# 3V3Supply.net
KiCad netlist of a schematic drawn in Altium Designer
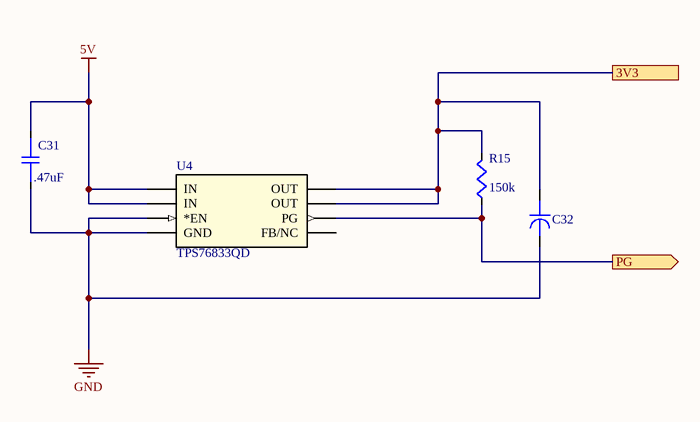
[diagram p0: 3V3Supply.SchDoc]

(export (version "E")
  (design (tool "Eeschema 10.0.6"))
  (components
    (comp (ref "C31")
      (value ".47uF")
      (footprint "C0603")
      (description "KEMET - C0603C474J4RACAUTO - CAP, 0.47µF, 16V, 5%, X7R, 0603")
      (fields (field (name "TOLERANCE") "5%"))
      (libsource (lib "DAQ") (part "C0603C474J4RACAUTO"))
    )
    (comp (ref "C32")
      (value "22UF TANT")
      (footprint "CAP_293D_D_VIS")
      (description "CAP TANT 22UF 10% 35V 2917")
      (fields (field (name "TOLERANCE") "10%") (field (name "VOLTAGE") "35V"))
      (libsource (lib "DAQ") (part "293D226X9035D2TE3"))
    )
    (comp (ref "R15")
      (value "150k")
      (footprint "R0603")
      (description "CRGCQ 0603 150K 1%")
      (fields (field (name "TOLERANCE") "5%"))
      (libsource (lib "DAQ") (part "CRGCQ0603F150K"))
    )
    (comp (ref "U4")
      (value "TPS76833QD")
      (footprint "D8_TEX")
      (description "3.3V Linear Voltage Regulator IC 1 Output 1A 8-SOIC")
      (fields (field (name "COPYRIGHT") "Copyright (C) 2018 Accelerated Designs. All rights reserved"))
      (libsource (lib "DAQ") (part "TPS76833QD"))
    )
  )
  (nets
    (net (code "1") (name "/3V3") (class "Default")
      (node (ref "C32") (pin "2") (pinfunction "2_2") (pintype "passive"))
      (node (ref "R15") (pin "2") (pinfunction "2_2") (pintype "passive"))
      (node (ref "U4") (pin "5") (pinfunction "OUT_5") (pintype "power_in"))
      (node (ref "U4") (pin "6") (pinfunction "OUT_6") (pintype "power_in"))
    )
    (net (code "2") (name "/PG") (class "Default")
      (node (ref "R15") (pin "1") (pinfunction "1_1") (pintype "passive"))
      (node (ref "U4") (pin "8") (pinfunction "PG_8") (pintype "output"))
    )
    (net (code "3") (name "5V") (class "Default")
      (node (ref "C31") (pin "2") (pinfunction "2_2") (pintype "passive"))
      (node (ref "U4") (pin "3") (pinfunction "IN_3") (pintype "power_in"))
      (node (ref "U4") (pin "4") (pinfunction "IN_4") (pintype "power_in"))
    )
    (net (code "4") (name "GND") (class "Default")
      (node (ref "C31") (pin "1") (pinfunction "1_1") (pintype "passive"))
      (node (ref "C32") (pin "1") (pinfunction "1_1") (pintype "passive"))
      (node (ref "U4") (pin "1") (pinfunction "GND_1") (pintype "power_in"))
      (node (ref "U4") (pin "2") (pinfunction "*EN_2") (pintype "input"))
    )
    (net (code "5") (name "unconnected-(U4-FB{slash}NC-Pad7)") (class "Default")
      (node (ref "U4") (pin "7") (pinfunction "FB/NC_7") (pintype "passive"))
    )
  )
)
